# wearable_sensor_v2_public.net
KiCad netlist of a schematic drawn in EAGLE
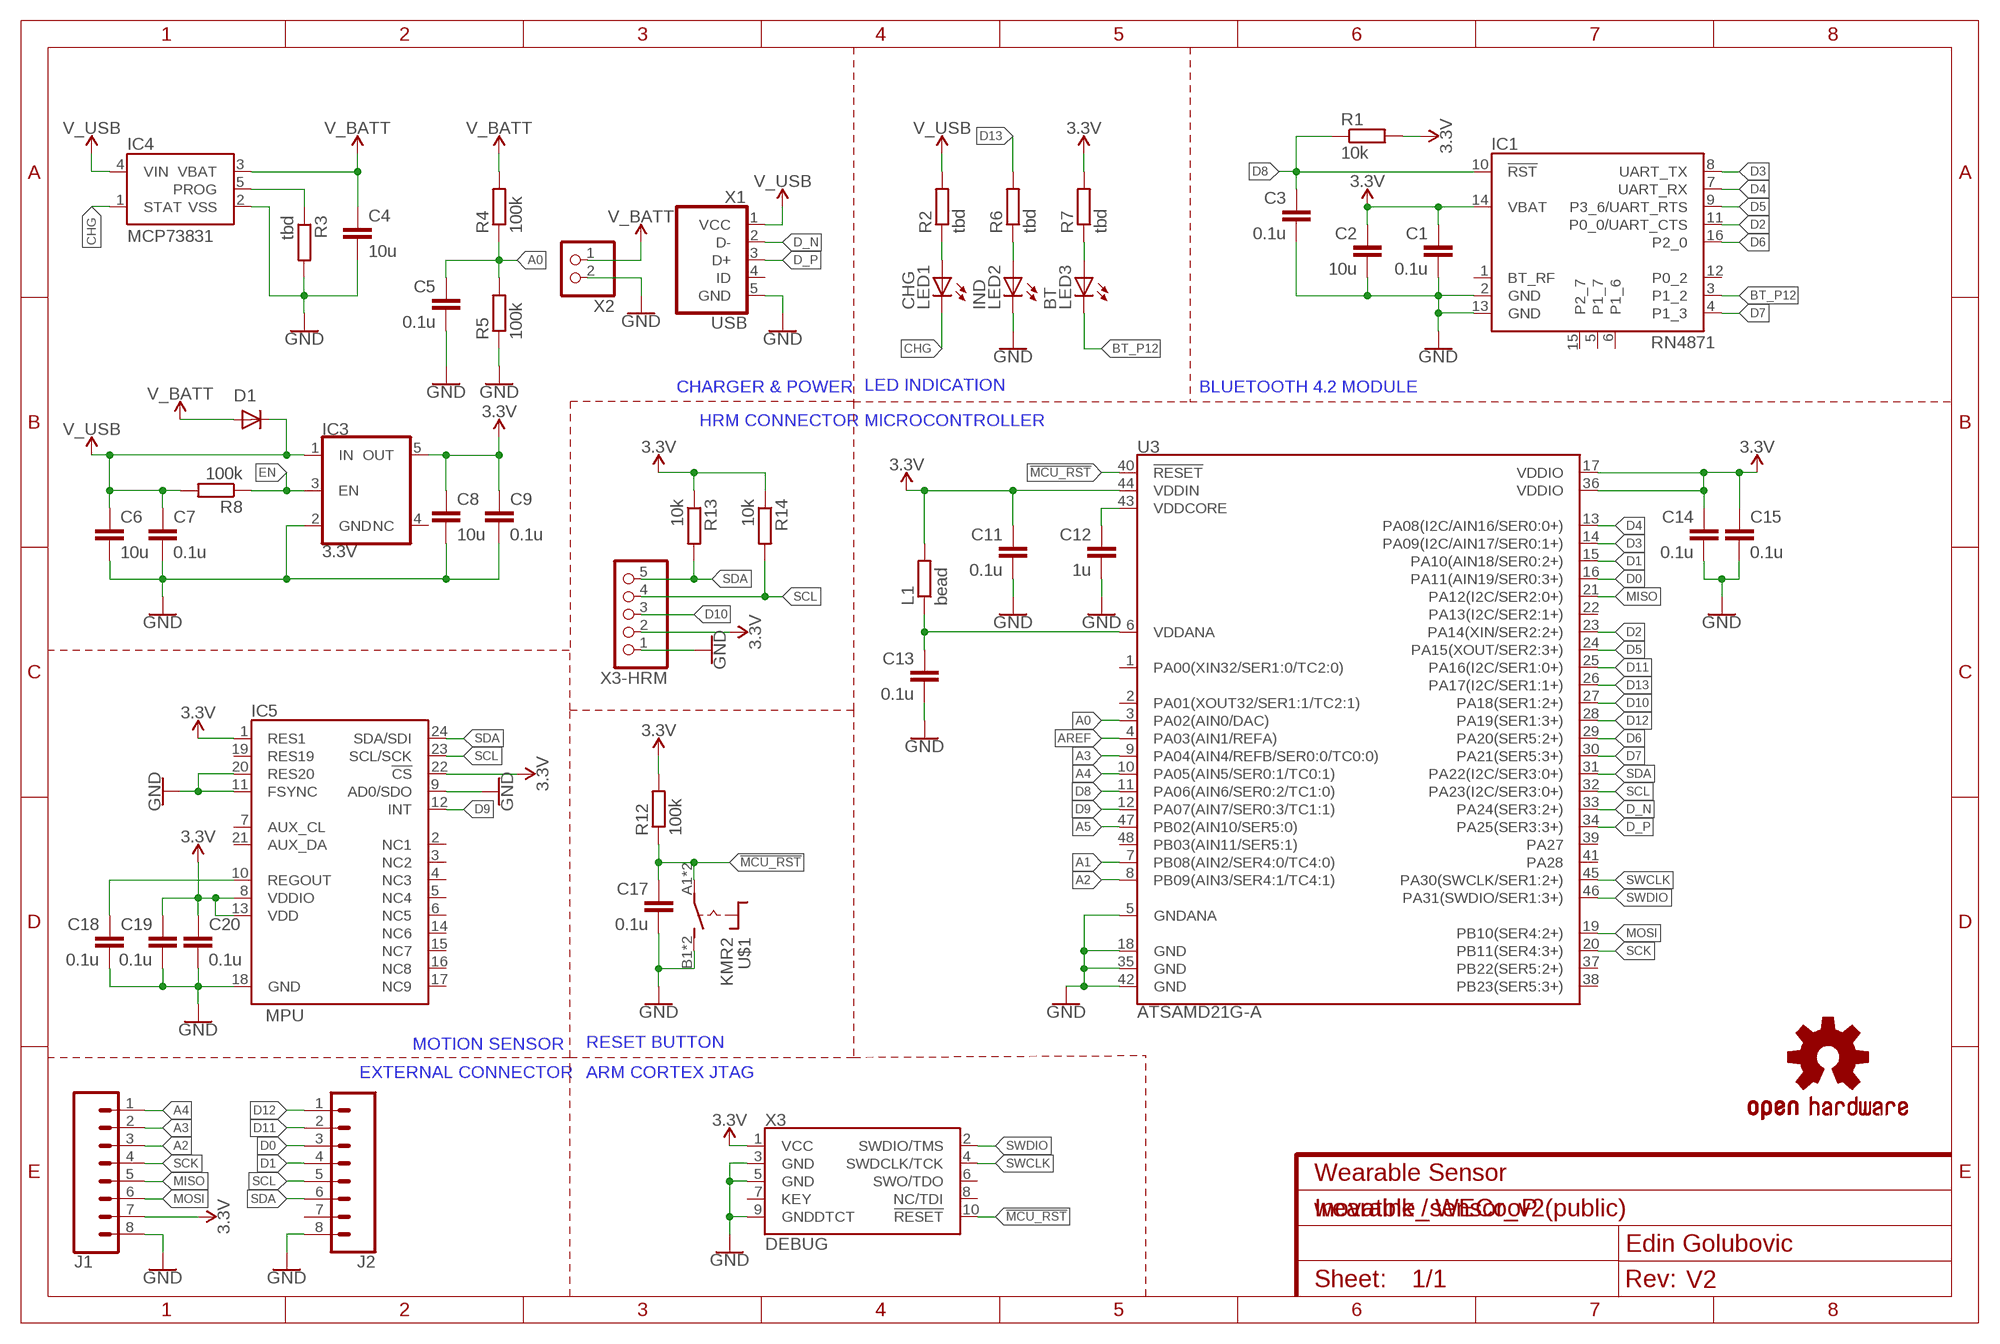
[diagram p0: schematic, sheet 1]

(export (version "E")
  (design (tool "Eeschema 10.0.6"))
  (components
    (comp (ref "C1")
      (value "0.1u")
      (footprint "eagle-import:C0805")
      (libsource (lib "eagle-import") (part "C-EUC0805"))
    )
    (comp (ref "C2")
      (value "10u")
      (footprint "eagle-import:C0805")
      (libsource (lib "eagle-import") (part "C-EUC0805"))
    )
    (comp (ref "C3")
      (value "0.1u")
      (footprint "eagle-import:C0805")
      (libsource (lib "eagle-import") (part "C-EUC0805"))
    )
    (comp (ref "C4")
      (value "10u")
      (footprint "eagle-import:C0805")
      (libsource (lib "eagle-import") (part "C-EUC0805"))
    )
    (comp (ref "C5")
      (value "0.1u")
      (footprint "eagle-import:C0805")
      (libsource (lib "eagle-import") (part "C-EUC0805"))
    )
    (comp (ref "C6")
      (value "10u")
      (footprint "eagle-import:C0805")
      (libsource (lib "eagle-import") (part "C-EUC0805"))
    )
    (comp (ref "C7")
      (value "0.1u")
      (footprint "eagle-import:C0805")
      (libsource (lib "eagle-import") (part "C-EUC0805"))
    )
    (comp (ref "C8")
      (value "10u")
      (footprint "eagle-import:C0805")
      (libsource (lib "eagle-import") (part "C-EUC0805"))
    )
    (comp (ref "C9")
      (value "0.1u")
      (footprint "eagle-import:C0805")
      (libsource (lib "eagle-import") (part "C-EUC0805"))
    )
    (comp (ref "C11")
      (value "0.1u")
      (footprint "eagle-import:C0805")
      (libsource (lib "eagle-import") (part "C-EUC0805"))
    )
    (comp (ref "C12")
      (value "1u")
      (footprint "eagle-import:C0805")
      (libsource (lib "eagle-import") (part "C-EUC0805"))
    )
    (comp (ref "C13")
      (value "0.1u")
      (footprint "eagle-import:C0805")
      (libsource (lib "eagle-import") (part "C-EUC0805"))
    )
    (comp (ref "C14")
      (value "0.1u")
      (footprint "eagle-import:C0805")
      (libsource (lib "eagle-import") (part "C-EUC0805"))
    )
    (comp (ref "C15")
      (value "0.1u")
      (footprint "eagle-import:C0805")
      (libsource (lib "eagle-import") (part "C-EUC0805"))
    )
    (comp (ref "C17")
      (value "0.1u")
      (footprint "eagle-import:C0805")
      (libsource (lib "eagle-import") (part "C-EUC0805"))
    )
    (comp (ref "C18")
      (value "0.1u")
      (footprint "eagle-import:C0805")
      (libsource (lib "eagle-import") (part "C-EUC0805"))
    )
    (comp (ref "C19")
      (value "0.1u")
      (footprint "eagle-import:C0805")
      (libsource (lib "eagle-import") (part "C-EUC0805"))
    )
    (comp (ref "C20")
      (value "0.1u")
      (footprint "eagle-import:C0805")
      (libsource (lib "eagle-import") (part "C-EUC0805"))
    )
    (comp (ref "D1")
      (value "DIODESOD-323F")
      (footprint "eagle-import:SOD-323F")
      (libsource (lib "eagle-import") (part "DIODESOD-323F"))
    )
    (comp (ref "IC1")
      (value "RN4871")
      (footprint "eagle-import:RN4871")
      (libsource (lib "eagle-import") (part "RN4871"))
    )
    (comp (ref "IC3")
      (value "3.3V")
      (footprint "eagle-import:SOT23-5")
      (libsource (lib "eagle-import") (part "V_REG_AP2112K-3.3V"))
    )
    (comp (ref "IC4")
      (value "MCP73831")
      (footprint "eagle-import:SOT23-5")
      (libsource (lib "eagle-import") (part "MCP73831"))
    )
    (comp (ref "IC5")
      (value "MPU")
      (footprint "eagle-import:MPU9250")
      (libsource (lib "eagle-import") (part "MPU-9250"))
    )
    (comp (ref "J1")
      (value "CONN_08SMD-MALE")
      (footprint "eagle-import:1X08_SMD_MALE")
      (libsource (lib "eagle-import") (part "CONN_08SMD-MALE"))
    )
    (comp (ref "J2")
      (value "CONN_08SMD-MALE")
      (footprint "eagle-import:1X08_SMD_MALE")
      (libsource (lib "eagle-import") (part "CONN_08SMD-MALE"))
    )
    (comp (ref "L1")
      (value "bead")
      (footprint "eagle-import:R0805")
      (libsource (lib "eagle-import") (part "R-EU_R0805"))
    )
    (comp (ref "LED1")
      (value "CHG")
      (footprint "eagle-import:CHIP-LED0805")
      (libsource (lib "eagle-import") (part "LEDCHIP-LED0805"))
    )
    (comp (ref "LED2")
      (value "IND")
      (footprint "eagle-import:CHIP-LED0805")
      (libsource (lib "eagle-import") (part "LEDCHIP-LED0805"))
    )
    (comp (ref "LED3")
      (value "BT")
      (footprint "eagle-import:CHIP-LED0805")
      (libsource (lib "eagle-import") (part "LEDCHIP-LED0805"))
    )
    (comp (ref "LOGO1")
      (value "OSHW-LOGOMINI")
      (footprint "eagle-import:OSHW-LOGO-MINI")
      (libsource (lib "eagle-import") (part "OSHW-LOGOMINI"))
    )
    (comp (ref "R1")
      (value "10k")
      (footprint "eagle-import:R0805")
      (libsource (lib "eagle-import") (part "R-EU_R0805"))
    )
    (comp (ref "R2")
      (value "tbd")
      (footprint "eagle-import:R0805")
      (libsource (lib "eagle-import") (part "R-EU_R0805"))
    )
    (comp (ref "R3")
      (value "tbd")
      (footprint "eagle-import:R0805")
      (libsource (lib "eagle-import") (part "R-EU_R0805"))
    )
    (comp (ref "R4")
      (value "100k")
      (footprint "eagle-import:R0805")
      (libsource (lib "eagle-import") (part "R-EU_R0805"))
    )
    (comp (ref "R5")
      (value "100k")
      (footprint "eagle-import:R0805")
      (libsource (lib "eagle-import") (part "R-EU_R0805"))
    )
    (comp (ref "R6")
      (value "tbd")
      (footprint "eagle-import:R0805")
      (libsource (lib "eagle-import") (part "R-EU_R0805"))
    )
    (comp (ref "R7")
      (value "tbd")
      (footprint "eagle-import:R0805")
      (libsource (lib "eagle-import") (part "R-EU_R0805"))
    )
    (comp (ref "R8")
      (value "100k")
      (footprint "eagle-import:R0805")
      (libsource (lib "eagle-import") (part "R-EU_R0805"))
    )
    (comp (ref "R12")
      (value "100k")
      (footprint "eagle-import:R0805")
      (libsource (lib "eagle-import") (part "R-EU_R0805"))
    )
    (comp (ref "R13")
      (value "10k")
      (footprint "eagle-import:R0805")
      (libsource (lib "eagle-import") (part "R-EU_R0805"))
    )
    (comp (ref "R14")
      (value "10k")
      (footprint "eagle-import:R0805")
      (libsource (lib "eagle-import") (part "R-EU_R0805"))
    )
    (comp (ref "U$1")
      (value "KMR2")
      (footprint "eagle-import:KMR2")
      (libsource (lib "eagle-import") (part "KMR2"))
    )
    (comp (ref "U3")
      (value "ATSAMD21G-A")
      (footprint "eagle-import:TQFP-48")
      (libsource (lib "eagle-import") (part "ATSAMD21G-A"))
    )
    (comp (ref "X1")
      (value "USB")
      (footprint "eagle-import:10118194-0001LF")
      (libsource (lib "eagle-import") (part "10118194-0001LF"))
    )
    (comp (ref "X2")
      (value "JST_2PIN-SMT-RA")
      (footprint "eagle-import:JST-PH-2-SMT-RA")
      (libsource (lib "eagle-import") (part "JST_2PIN-SMT-RA"))
    )
    (comp (ref "X3")
      (value "DEBUG")
      (footprint "eagle-import:2X5-PTH-1.27MM")
      (libsource (lib "eagle-import") (part "CORTEX_DEBUG_PTH"))
    )
    (comp (ref "X3-HRM")
      (value "PINHD-1X5")
      (footprint "eagle-import:1X05")
      (libsource (lib "eagle-import") (part "PINHD-1X5"))
    )
  )
  (nets
    (net (code "1") (name "/~{MCU_RST}") (class "Default")
      (node (ref "C17") (pin "1") (pinfunction "1_1") (pintype "passive"))
      (node (ref "R12") (pin "1") (pinfunction "1_1") (pintype "passive"))
      (node (ref "U$1") (pin "A1") (pinfunction "P_A1") (pintype "passive"))
      (node (ref "U$1") (pin "A2") (pinfunction "P_A2") (pintype "passive"))
      (node (ref "U3") (pin "40") (pinfunction "~{RESET}_40") (pintype "bidirectional"))
      (node (ref "X3") (pin "10") (pinfunction "~{RESET}_10") (pintype "bidirectional"))
    )
    (net (code "2") (name "3.3V") (class "Default")
      (node (ref "C1") (pin "1") (pinfunction "1_1") (pintype "passive"))
      (node (ref "C11") (pin "1") (pinfunction "1_1") (pintype "passive"))
      (node (ref "C14") (pin "1") (pinfunction "1_1") (pintype "passive"))
      (node (ref "C15") (pin "1") (pinfunction "1_1") (pintype "passive"))
      (node (ref "C19") (pin "1") (pinfunction "1_1") (pintype "passive"))
      (node (ref "C2") (pin "1") (pinfunction "1_1") (pintype "passive"))
      (node (ref "C20") (pin "1") (pinfunction "1_1") (pintype "passive"))
      (node (ref "C8") (pin "1") (pinfunction "1_1") (pintype "passive"))
      (node (ref "C9") (pin "1") (pinfunction "1_1") (pintype "passive"))
      (node (ref "IC1") (pin "14") (pinfunction "VBAT_14") (pintype "bidirectional"))
      (node (ref "IC3") (pin "5") (pinfunction "OUT_5") (pintype "passive"))
      (node (ref "IC5") (pin "1") (pinfunction "RES1_1") (pintype "bidirectional"))
      (node (ref "IC5") (pin "13") (pinfunction "VDD_13") (pintype "power_in"))
      (node (ref "IC5") (pin "22") (pinfunction "~{CS}_22") (pintype "bidirectional"))
      (node (ref "IC5") (pin "8") (pinfunction "VDDIO_8") (pintype "power_in"))
      (node (ref "J1") (pin "7") (pinfunction "7_7") (pintype "passive"))
      (node (ref "L1") (pin "2") (pinfunction "2_2") (pintype "passive"))
      (node (ref "R1") (pin "2") (pinfunction "2_2") (pintype "passive"))
      (node (ref "R12") (pin "2") (pinfunction "2_2") (pintype "passive"))
      (node (ref "R13") (pin "1") (pinfunction "1_1") (pintype "passive"))
      (node (ref "R14") (pin "1") (pinfunction "1_1") (pintype "passive"))
      (node (ref "R7") (pin "2") (pinfunction "2_2") (pintype "passive"))
      (node (ref "U3") (pin "17") (pinfunction "VDDIO_17") (pintype "bidirectional"))
      (node (ref "U3") (pin "36") (pinfunction "VDDIO_36") (pintype "bidirectional"))
      (node (ref "U3") (pin "44") (pinfunction "VDDIN_44") (pintype "bidirectional"))
      (node (ref "X3") (pin "1") (pinfunction "VCC_1") (pintype "bidirectional"))
      (node (ref "X3-HRM") (pin "2") (pinfunction "2_2") (pintype "passive"))
    )
    (net (code "3") (name "A0") (class "Default")
      (node (ref "C5") (pin "1") (pinfunction "1_1") (pintype "passive"))
      (node (ref "R4") (pin "1") (pinfunction "1_1") (pintype "passive"))
      (node (ref "R5") (pin "2") (pinfunction "2_2") (pintype "passive"))
      (node (ref "U3") (pin "3") (pinfunction "PA02(AIN0/DAC)_3") (pintype "bidirectional"))
    )
    (net (code "4") (name "A1") (class "Default")
      (node (ref "U3") (pin "7") (pinfunction "PB08(AIN2/SER4:0/TC4:0)_7") (pintype "bidirectional"))
    )
    (net (code "5") (name "A2") (class "Default")
      (node (ref "J1") (pin "3") (pinfunction "3_3") (pintype "passive"))
      (node (ref "U3") (pin "8") (pinfunction "PB09(AIN3/SER4:1/TC4:1)_8") (pintype "bidirectional"))
    )
    (net (code "6") (name "A3") (class "Default")
      (node (ref "J1") (pin "2") (pinfunction "2_2") (pintype "passive"))
      (node (ref "U3") (pin "9") (pinfunction "PA04(AIN4/REFB/SER0:0/TC0:0)_9") (pintype "bidirectional"))
    )
    (net (code "7") (name "A4") (class "Default")
      (node (ref "J1") (pin "1") (pinfunction "1_1") (pintype "passive"))
      (node (ref "U3") (pin "10") (pinfunction "PA05(AIN5/SER0:1/TC0:1)_10") (pintype "bidirectional"))
    )
    (net (code "8") (name "A5") (class "Default")
      (node (ref "U3") (pin "47") (pinfunction "PB02(AIN10/SER5:0)_47") (pintype "bidirectional"))
    )
    (net (code "9") (name "AREF") (class "Default")
      (node (ref "U3") (pin "4") (pinfunction "PA03(AIN1/REFA)_4") (pintype "bidirectional"))
    )
    (net (code "10") (name "BT_P12") (class "Default")
      (node (ref "IC1") (pin "3") (pinfunction "P1_2_3") (pintype "bidirectional"))
      (node (ref "LED3") (pin "C") (pinfunction "C_C") (pintype "passive"))
    )
    (net (code "11") (name "CHG") (class "Default")
      (node (ref "IC4") (pin "1") (pinfunction "STAT_1") (pintype "output"))
      (node (ref "LED1") (pin "C") (pinfunction "C_C") (pintype "passive"))
    )
    (net (code "12") (name "D0") (class "Default")
      (node (ref "J2") (pin "3") (pinfunction "3_3") (pintype "passive"))
      (node (ref "U3") (pin "16") (pinfunction "PA11(AIN19/SER0:3+)_16") (pintype "bidirectional"))
    )
    (net (code "13") (name "D1") (class "Default")
      (node (ref "J2") (pin "4") (pinfunction "4_4") (pintype "passive"))
      (node (ref "U3") (pin "15") (pinfunction "PA10(AIN18/SER0:2+)_15") (pintype "bidirectional"))
    )
    (net (code "14") (name "D2") (class "Default")
      (node (ref "IC1") (pin "11") (pinfunction "P0_0/UART_CTS_11") (pintype "bidirectional"))
      (node (ref "U3") (pin "23") (pinfunction "PA14(XIN/SER2:2+)_23") (pintype "bidirectional"))
    )
    (net (code "15") (name "D3") (class "Default")
      (node (ref "IC1") (pin "8") (pinfunction "UART_TX_8") (pintype "bidirectional"))
      (node (ref "U3") (pin "14") (pinfunction "PA09(I2C/AIN17/SER0:1+)_14") (pintype "bidirectional"))
    )
    (net (code "16") (name "D4") (class "Default")
      (node (ref "IC1") (pin "7") (pinfunction "UART_RX_7") (pintype "bidirectional"))
      (node (ref "U3") (pin "13") (pinfunction "PA08(I2C/AIN16/SER0:0+)_13") (pintype "bidirectional"))
    )
    (net (code "17") (name "D5") (class "Default")
      (node (ref "IC1") (pin "9") (pinfunction "P3_6/UART_RTS_9") (pintype "bidirectional"))
      (node (ref "U3") (pin "24") (pinfunction "PA15(XOUT/SER2:3+)_24") (pintype "bidirectional"))
    )
    (net (code "18") (name "D6") (class "Default")
      (node (ref "IC1") (pin "16") (pinfunction "P2_0_16") (pintype "bidirectional"))
      (node (ref "U3") (pin "29") (pinfunction "PA20(SER5:2+)_29") (pintype "bidirectional"))
    )
    (net (code "19") (name "D7") (class "Default")
      (node (ref "IC1") (pin "4") (pinfunction "P1_3_4") (pintype "bidirectional"))
      (node (ref "U3") (pin "30") (pinfunction "PA21(SER5:3+)_30") (pintype "bidirectional"))
    )
    (net (code "20") (name "D8") (class "Default")
      (node (ref "C3") (pin "1") (pinfunction "1_1") (pintype "passive"))
      (node (ref "IC1") (pin "10") (pinfunction "~{RST}_10") (pintype "bidirectional"))
      (node (ref "R1") (pin "1") (pinfunction "1_1") (pintype "passive"))
      (node (ref "U3") (pin "11") (pinfunction "PA06(AIN6/SER0:2/TC1:0)_11") (pintype "bidirectional"))
    )
    (net (code "21") (name "D9") (class "Default")
      (node (ref "IC5") (pin "12") (pinfunction "INT_12") (pintype "bidirectional"))
      (node (ref "U3") (pin "12") (pinfunction "PA07(AIN7/SER0:3/TC1:1)_12") (pintype "bidirectional"))
    )
    (net (code "22") (name "D10") (class "Default")
      (node (ref "U3") (pin "27") (pinfunction "PA18(SER1:2+)_27") (pintype "bidirectional"))
      (node (ref "X3-HRM") (pin "3") (pinfunction "3_3") (pintype "passive"))
    )
    (net (code "23") (name "D11") (class "Default")
      (node (ref "J2") (pin "2") (pinfunction "2_2") (pintype "passive"))
      (node (ref "U3") (pin "25") (pinfunction "PA16(I2C/SER1:0+)_25") (pintype "bidirectional"))
    )
    (net (code "24") (name "D12") (class "Default")
      (node (ref "J2") (pin "1") (pinfunction "1_1") (pintype "passive"))
      (node (ref "U3") (pin "28") (pinfunction "PA19(SER1:3+)_28") (pintype "bidirectional"))
    )
    (net (code "25") (name "D13") (class "Default")
      (node (ref "R6") (pin "2") (pinfunction "2_2") (pintype "passive"))
      (node (ref "U3") (pin "26") (pinfunction "PA17(I2C/SER1:1+)_26") (pintype "bidirectional"))
    )
    (net (code "26") (name "D_N") (class "Default")
      (node (ref "U3") (pin "33") (pinfunction "PA24(SER3:2+)_33") (pintype "bidirectional"))
      (node (ref "X1") (pin "2") (pinfunction "D-_2") (pintype "bidirectional"))
    )
    (net (code "27") (name "D_P") (class "Default")
      (node (ref "U3") (pin "34") (pinfunction "PA25(SER3:3+)_34") (pintype "bidirectional"))
      (node (ref "X1") (pin "3") (pinfunction "D+_3") (pintype "bidirectional"))
    )
    (net (code "28") (name "EN") (class "Default")
      (node (ref "IC3") (pin "3") (pinfunction "EN_3") (pintype "input"))
      (node (ref "R8") (pin "1") (pinfunction "1_1") (pintype "passive"))
    )
    (net (code "29") (name "GND") (class "Default")
      (node (ref "C1") (pin "2") (pinfunction "2_2") (pintype "passive"))
      (node (ref "C11") (pin "2") (pinfunction "2_2") (pintype "passive"))
      (node (ref "C12") (pin "2") (pinfunction "2_2") (pintype "passive"))
      (node (ref "C13") (pin "2") (pinfunction "2_2") (pintype "passive"))
      (node (ref "C14") (pin "2") (pinfunction "2_2") (pintype "passive"))
      (node (ref "C15") (pin "2") (pinfunction "2_2") (pintype "passive"))
      (node (ref "C17") (pin "2") (pinfunction "2_2") (pintype "passive"))
      (node (ref "C18") (pin "2") (pinfunction "2_2") (pintype "passive"))
      (node (ref "C19") (pin "2") (pinfunction "2_2") (pintype "passive"))
      (node (ref "C2") (pin "2") (pinfunction "2_2") (pintype "passive"))
      (node (ref "C20") (pin "2") (pinfunction "2_2") (pintype "passive"))
      (node (ref "C3") (pin "2") (pinfunction "2_2") (pintype "passive"))
      (node (ref "C4") (pin "2") (pinfunction "2_2") (pintype "passive"))
      (node (ref "C5") (pin "2") (pinfunction "2_2") (pintype "passive"))
      (node (ref "C6") (pin "2") (pinfunction "2_2") (pintype "passive"))
      (node (ref "C7") (pin "2") (pinfunction "2_2") (pintype "passive"))
      (node (ref "C8") (pin "2") (pinfunction "2_2") (pintype "passive"))
      (node (ref "C9") (pin "2") (pinfunction "2_2") (pintype "passive"))
      (node (ref "IC1") (pin "13") (pinfunction "GND_13") (pintype "bidirectional"))
      (node (ref "IC1") (pin "2") (pinfunction "GND_2") (pintype "bidirectional"))
      (node (ref "IC3") (pin "2") (pinfunction "GND_2") (pintype "input"))
      (node (ref "IC4") (pin "2") (pinfunction "VSS_2") (pintype "power_in"))
      (node (ref "IC5") (pin "11") (pinfunction "FSYNC_11") (pintype "bidirectional"))
      (node (ref "IC5") (pin "18") (pinfunction "GND_18") (pintype "power_in"))
      (node (ref "IC5") (pin "20") (pinfunction "RES20_20") (pintype "bidirectional"))
      (node (ref "IC5") (pin "9") (pinfunction "AD0/SDO_9") (pintype "bidirectional"))
      (node (ref "J1") (pin "8") (pinfunction "8_8") (pintype "passive"))
      (node (ref "J2") (pin "8") (pinfunction "8_8") (pintype "passive"))
      (node (ref "LED2") (pin "C") (pinfunction "C_C") (pintype "passive"))
      (node (ref "R3") (pin "2") (pinfunction "2_2") (pintype "passive"))
      (node (ref "R5") (pin "1") (pinfunction "1_1") (pintype "passive"))
      (node (ref "U$1") (pin "B1") (pinfunction "S_B1") (pintype "passive"))
      (node (ref "U$1") (pin "B2") (pinfunction "S_B2") (pintype "passive"))
      (node (ref "U3") (pin "18") (pinfunction "GND_18") (pintype "bidirectional"))
      (node (ref "U3") (pin "35") (pinfunction "GND_35") (pintype "bidirectional"))
      (node (ref "U3") (pin "42") (pinfunction "GND_42") (pintype "bidirectional"))
      (node (ref "U3") (pin "5") (pinfunction "GNDANA_5") (pintype "bidirectional"))
      (node (ref "X1") (pin "5") (pinfunction "GND_5") (pintype "bidirectional"))
      (node (ref "X2") (pin "2") (pinfunction "1_2") (pintype "passive"))
      (node (ref "X3") (pin "3") (pinfunction "GND_3") (pintype "bidirectional"))
      (node (ref "X3") (pin "5") (pinfunction "GND_5") (pintype "bidirectional"))
      (node (ref "X3") (pin "9") (pinfunction "GNDDTCT_9") (pintype "bidirectional"))
      (node (ref "X3-HRM") (pin "1") (pinfunction "1_1") (pintype "passive"))
    )
    (net (code "30") (name "MISO") (class "Default")
      (node (ref "J1") (pin "5") (pinfunction "5_5") (pintype "passive"))
      (node (ref "U3") (pin "21") (pinfunction "PA12(I2C/SER2:0+)_21") (pintype "bidirectional"))
    )
    (net (code "31") (name "MOSI") (class "Default")
      (node (ref "J1") (pin "6") (pinfunction "6_6") (pintype "passive"))
      (node (ref "U3") (pin "19") (pinfunction "PB10(SER4:2+)_19") (pintype "bidirectional"))
    )
    (net (code "32") (name "Net-(IC4-PROG)") (class "Default")
      (node (ref "IC4") (pin "5") (pinfunction "PROG_5") (pintype "input"))
      (node (ref "R3") (pin "1") (pinfunction "1_1") (pintype "passive"))
    )
    (net (code "33") (name "Net-(IC5-REGOUT)") (class "Default")
      (node (ref "C18") (pin "1") (pinfunction "1_1") (pintype "passive"))
      (node (ref "IC5") (pin "10") (pinfunction "REGOUT_10") (pintype "power_in"))
    )
    (net (code "34") (name "Net-(LED1-PadA)") (class "Default")
      (node (ref "LED1") (pin "A") (pinfunction "A_A") (pintype "passive"))
      (node (ref "R2") (pin "1") (pinfunction "1_1") (pintype "passive"))
    )
    (net (code "35") (name "Net-(LED2-PadA)") (class "Default")
      (node (ref "LED2") (pin "A") (pinfunction "A_A") (pintype "passive"))
      (node (ref "R6") (pin "1") (pinfunction "1_1") (pintype "passive"))
    )
    (net (code "36") (name "Net-(LED3-PadA)") (class "Default")
      (node (ref "LED3") (pin "A") (pinfunction "A_A") (pintype "passive"))
      (node (ref "R7") (pin "1") (pinfunction "1_1") (pintype "passive"))
    )
    (net (code "37") (name "Net-(U3-VDDANA)") (class "Default")
      (node (ref "C13") (pin "1") (pinfunction "1_1") (pintype "passive"))
      (node (ref "L1") (pin "1") (pinfunction "1_1") (pintype "passive"))
      (node (ref "U3") (pin "6") (pinfunction "VDDANA_6") (pintype "bidirectional"))
    )
    (net (code "38") (name "Net-(U3-VDDCORE)") (class "Default")
      (node (ref "C12") (pin "1") (pinfunction "1_1") (pintype "passive"))
      (node (ref "U3") (pin "43") (pinfunction "VDDCORE_43") (pintype "bidirectional"))
    )
    (net (code "39") (name "SCK") (class "Default")
      (node (ref "J1") (pin "4") (pinfunction "4_4") (pintype "passive"))
      (node (ref "U3") (pin "20") (pinfunction "PB11(SER4:3+)_20") (pintype "bidirectional"))
    )
    (net (code "40") (name "SCL") (class "Default")
      (node (ref "IC5") (pin "23") (pinfunction "SCL/SCK_23") (pintype "bidirectional"))
      (node (ref "J2") (pin "5") (pinfunction "5_5") (pintype "passive"))
      (node (ref "R14") (pin "2") (pinfunction "2_2") (pintype "passive"))
      (node (ref "U3") (pin "32") (pinfunction "PA23(I2C/SER3:0+)_32") (pintype "bidirectional"))
      (node (ref "X3-HRM") (pin "4") (pinfunction "4_4") (pintype "passive"))
    )
    (net (code "41") (name "SDA") (class "Default")
      (node (ref "IC5") (pin "24") (pinfunction "SDA/SDI_24") (pintype "bidirectional"))
      (node (ref "J2") (pin "6") (pinfunction "6_6") (pintype "passive"))
      (node (ref "R13") (pin "2") (pinfunction "2_2") (pintype "passive"))
      (node (ref "U3") (pin "31") (pinfunction "PA22(I2C/SER3:0+)_31") (pintype "bidirectional"))
      (node (ref "X3-HRM") (pin "5") (pinfunction "5_5") (pintype "passive"))
    )
    (net (code "42") (name "SWCLK") (class "Default")
      (node (ref "U3") (pin "45") (pinfunction "PA30(SWCLK/SER1:2+)_45") (pintype "bidirectional"))
      (node (ref "X3") (pin "4") (pinfunction "SWDCLK/TCK_4") (pintype "bidirectional"))
    )
    (net (code "43") (name "SWDIO") (class "Default")
      (node (ref "U3") (pin "46") (pinfunction "PA31(SWDIO/SER1:3+)_46") (pintype "bidirectional"))
      (node (ref "X3") (pin "2") (pinfunction "SWDIO/TMS_2") (pintype "bidirectional"))
    )
    (net (code "44") (name "V_BATT") (class "Default")
      (node (ref "C4") (pin "1") (pinfunction "1_1") (pintype "passive"))
      (node (ref "D1") (pin "A") (pinfunction "A_A") (pintype "passive"))
      (node (ref "IC4") (pin "3") (pinfunction "VBAT_3") (pintype "power_in"))
      (node (ref "R4") (pin "2") (pinfunction "2_2") (pintype "passive"))
      (node (ref "X2") (pin "1") (pinfunction "2_1") (pintype "passive"))
    )
    (net (code "45") (name "V_USB") (class "Default")
      (node (ref "C6") (pin "1") (pinfunction "1_1") (pintype "passive"))
      (node (ref "C7") (pin "1") (pinfunction "1_1") (pintype "passive"))
      (node (ref "D1") (pin "C") (pinfunction "C_C") (pintype "passive"))
      (node (ref "IC3") (pin "1") (pinfunction "IN_1") (pintype "input"))
      (node (ref "IC4") (pin "4") (pinfunction "VIN_4") (pintype "power_in"))
      (node (ref "R2") (pin "2") (pinfunction "2_2") (pintype "passive"))
      (node (ref "R8") (pin "2") (pinfunction "2_2") (pintype "passive"))
      (node (ref "X1") (pin "1") (pinfunction "VCC_1") (pintype "bidirectional"))
    )
    (net (code "46") (name "unconnected-(IC1-BT_RF-Pad1)") (class "Default")
      (node (ref "IC1") (pin "1") (pinfunction "BT_RF_1") (pintype "bidirectional"))
    )
    (net (code "47") (name "unconnected-(IC1-P0_2-Pad12)") (class "Default")
      (node (ref "IC1") (pin "12") (pinfunction "P0_2_12") (pintype "bidirectional"))
    )
    (net (code "48") (name "unconnected-(IC1-P1_6-Pad6)") (class "Default")
      (node (ref "IC1") (pin "6") (pinfunction "P1_6_6") (pintype "bidirectional"))
    )
    (net (code "49") (name "unconnected-(IC1-P1_7-Pad5)") (class "Default")
      (node (ref "IC1") (pin "5") (pinfunction "P1_7_5") (pintype "bidirectional"))
    )
    (net (code "50") (name "unconnected-(IC1-P2_7-Pad15)") (class "Default")
      (node (ref "IC1") (pin "15") (pinfunction "P2_7_15") (pintype "bidirectional"))
    )
    (net (code "51") (name "unconnected-(IC3-NC-Pad4)") (class "Default")
      (node (ref "IC3") (pin "4") (pinfunction "NC_4") (pintype "no_connect"))
    )
    (net (code "52") (name "unconnected-(IC5-AUX_CL-Pad7)") (class "Default")
      (node (ref "IC5") (pin "7") (pinfunction "AUX_CL_7") (pintype "bidirectional"))
    )
    (net (code "53") (name "unconnected-(IC5-AUX_DA-Pad21)") (class "Default")
      (node (ref "IC5") (pin "21") (pinfunction "AUX_DA_21") (pintype "bidirectional"))
    )
    (net (code "54") (name "unconnected-(IC5-NC1-Pad2)") (class "Default")
      (node (ref "IC5") (pin "2") (pinfunction "NC1_2") (pintype "open_collector"))
    )
    (net (code "55") (name "unconnected-(IC5-NC2-Pad3)") (class "Default")
      (node (ref "IC5") (pin "3") (pinfunction "NC2_3") (pintype "open_collector"))
    )
    (net (code "56") (name "unconnected-(IC5-NC3-Pad4)") (class "Default")
      (node (ref "IC5") (pin "4") (pinfunction "NC3_4") (pintype "open_collector"))
    )
    (net (code "57") (name "unconnected-(IC5-NC4-Pad5)") (class "Default")
      (node (ref "IC5") (pin "5") (pinfunction "NC4_5") (pintype "open_collector"))
    )
    (net (code "58") (name "unconnected-(IC5-NC5-Pad6)") (class "Default")
      (node (ref "IC5") (pin "6") (pinfunction "NC5_6") (pintype "open_collector"))
    )
    (net (code "59") (name "unconnected-(IC5-NC6-Pad14)") (class "Default")
      (node (ref "IC5") (pin "14") (pinfunction "NC6_14") (pintype "open_collector"))
    )
    (net (code "60") (name "unconnected-(IC5-NC7-Pad15)") (class "Default")
      (node (ref "IC5") (pin "15") (pinfunction "NC7_15") (pintype "open_collector"))
    )
    (net (code "61") (name "unconnected-(IC5-NC8-Pad16)") (class "Default")
      (node (ref "IC5") (pin "16") (pinfunction "NC8_16") (pintype "open_collector"))
    )
    (net (code "62") (name "unconnected-(IC5-NC9-Pad17)") (class "Default")
      (node (ref "IC5") (pin "17") (pinfunction "NC9_17") (pintype "open_collector"))
    )
    (net (code "63") (name "unconnected-(IC5-RES19-Pad19)") (class "Default")
      (node (ref "IC5") (pin "19") (pinfunction "RES19_19") (pintype "bidirectional"))
    )
    (net (code "64") (name "unconnected-(J2-Pad7)") (class "Default")
      (node (ref "J2") (pin "7") (pinfunction "7_7") (pintype "passive"))
    )
    (net (code "65") (name "unconnected-(U3-PA00(XIN32{slash}SER1:0{slash}TC2:0)-Pad1)") (class "Default")
      (node (ref "U3") (pin "1") (pinfunction "PA00(XIN32/SER1:0/TC2:0)_1") (pintype "bidirectional"))
    )
    (net (code "66") (name "unconnected-(U3-PA01(XOUT32{slash}SER1:1{slash}TC2:1)-Pad2)") (class "Default")
      (node (ref "U3") (pin "2") (pinfunction "PA01(XOUT32/SER1:1/TC2:1)_2") (pintype "bidirectional"))
    )
    (net (code "67") (name "unconnected-(U3-PA13(I2C{slash}SER2:1+)-Pad22)") (class "Default")
      (node (ref "U3") (pin "22") (pinfunction "PA13(I2C/SER2:1+)_22") (pintype "bidirectional"))
    )
    (net (code "68") (name "unconnected-(U3-PA27-Pad39)") (class "Default")
      (node (ref "U3") (pin "39") (pinfunction "PA27_39") (pintype "bidirectional"))
    )
    (net (code "69") (name "unconnected-(U3-PA28-Pad41)") (class "Default")
      (node (ref "U3") (pin "41") (pinfunction "PA28_41") (pintype "bidirectional"))
    )
    (net (code "70") (name "unconnected-(U3-PB03(AIN11{slash}SER5:1)-Pad48)") (class "Default")
      (node (ref "U3") (pin "48") (pinfunction "PB03(AIN11/SER5:1)_48") (pintype "bidirectional"))
    )
    (net (code "71") (name "unconnected-(U3-PB22(SER5:2+)-Pad37)") (class "Default")
      (node (ref "U3") (pin "37") (pinfunction "PB22(SER5:2+)_37") (pintype "bidirectional"))
    )
    (net (code "72") (name "unconnected-(U3-PB23(SER5:3+)-Pad38)") (class "Default")
      (node (ref "U3") (pin "38") (pinfunction "PB23(SER5:3+)_38") (pintype "bidirectional"))
    )
    (net (code "73") (name "unconnected-(X1-ID-Pad4)") (class "Default")
      (node (ref "X1") (pin "4") (pinfunction "ID_4") (pintype "bidirectional"))
    )
    (net (code "74") (name "unconnected-(X3-KEY-Pad7)") (class "Default")
      (node (ref "X3") (pin "7") (pinfunction "KEY_7") (pintype "bidirectional"))
    )
    (net (code "75") (name "unconnected-(X3-NC{slash}TDI-Pad8)") (class "Default")
      (node (ref "X3") (pin "8") (pinfunction "NC/TDI_8") (pintype "bidirectional"))
    )
    (net (code "76") (name "unconnected-(X3-SWO{slash}TDO-Pad6)") (class "Default")
      (node (ref "X3") (pin "6") (pinfunction "SWO/TDO_6") (pintype "bidirectional"))
    )
  )
)
